# DAC_Schematic.net
KiCad netlist of a schematic drawn in Altium Designer
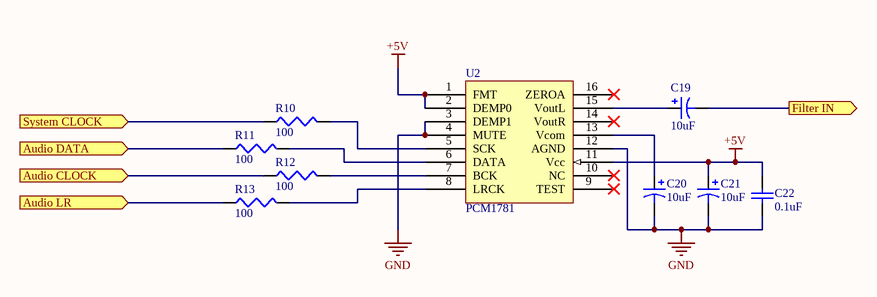
[diagram p0: DAC.Schematic.SchDoc]

(export (version "E")
  (design (tool "Eeschema 10.0.6"))
  (components
    (comp (ref "C19")
      (value "10uF")
      (footprint "CAPC1608N - cap")
      (description "Polarized Capacitor (Radial)")
      (fields (field (name "PUBLISHER") "Altium Limited"))
      (libsource (lib "Miscellaneous Devices") (part "Cap Pol1"))
    )
    (comp (ref "C20")
      (value "10uF")
      (footprint "CAPC1608N - cap")
      (description "Polarized Capacitor (Radial)")
      (fields (field (name "PUBLISHER") "Altium Limited"))
      (libsource (lib "Miscellaneous Devices") (part "Cap Pol1"))
    )
    (comp (ref "C21")
      (value "10uF")
      (footprint "CAPC1608N - cap")
      (description "Polarized Capacitor (Radial)")
      (fields (field (name "PUBLISHER") "Altium Limited"))
      (libsource (lib "Miscellaneous Devices") (part "Cap Pol1"))
    )
    (comp (ref "C22")
      (value "0.1uF")
      (footprint "CAPC1608N - cap")
      (description "Capacitor (Semiconductor SIM Model)")
      (fields (field (name "PUBLISHER") "Altium Limited"))
      (libsource (lib "Miscellaneous Devices") (part "Cap Semi"))
    )
    (comp (ref "R10")
      (value "100")
      (footprint "CAPC1608N")
      (description "Resistor")
      (fields (field (name "PUBLISHER") "Altium Limited"))
      (libsource (lib "Miscellaneous Devices") (part "Res3"))
    )
    (comp (ref "R11")
      (value "100")
      (footprint "CAPC1608N")
      (description "Resistor")
      (fields (field (name "PUBLISHER") "Altium Limited"))
      (libsource (lib "Miscellaneous Devices") (part "Res3"))
    )
    (comp (ref "R12")
      (value "100")
      (footprint "CAPC1608N")
      (description "Resistor")
      (fields (field (name "PUBLISHER") "Altium Limited"))
      (libsource (lib "Miscellaneous Devices") (part "Res3"))
    )
    (comp (ref "R13")
      (value "100")
      (footprint "CAPC1608N")
      (description "Resistor")
      (fields (field (name "PUBLISHER") "Altium Limited"))
      (libsource (lib "Miscellaneous Devices") (part "Res3"))
    )
    (comp (ref "U2")
      (value "PCM1781")
      (footprint "PCM1781")
      (libsource (lib "SynthyTwo.Components") (part "PCM1781 DAC"))
    )
  )
  (nets
    (net (code "1") (name "+5V") (class "Default")
      (node (ref "C21") (pin "1") (pinfunction "1_1") (pintype "passive"))
      (node (ref "C22") (pin "2") (pinfunction "2_2") (pintype "passive"))
      (node (ref "U2") (pin "1") (pinfunction "FMT_1") (pintype "passive"))
      (node (ref "U2") (pin "11") (pinfunction "Vcc_11") (pintype "input"))
      (node (ref "U2") (pin "2") (pinfunction "DEMP0_2") (pintype "passive"))
    )
    (net (code "2") (name "/Audio CLOCK") (class "Default")
      (node (ref "R12") (pin "1") (pinfunction "1_1") (pintype "passive"))
    )
    (net (code "3") (name "/Audio DATA") (class "Default")
      (node (ref "R11") (pin "1") (pinfunction "1_1") (pintype "passive"))
    )
    (net (code "4") (name "/Audio LR") (class "Default")
      (node (ref "R13") (pin "1") (pinfunction "1_1") (pintype "passive"))
    )
    (net (code "5") (name "/Filter IN") (class "Default")
      (node (ref "C19") (pin "2") (pinfunction "2_2") (pintype "passive"))
    )
    (net (code "6") (name "/System CLOCK") (class "Default")
      (node (ref "R10") (pin "1") (pinfunction "1_1") (pintype "passive"))
    )
    (net (code "7") (name "GND") (class "Default")
      (node (ref "C20") (pin "2") (pinfunction "2_2") (pintype "passive"))
      (node (ref "C21") (pin "2") (pinfunction "2_2") (pintype "passive"))
      (node (ref "C22") (pin "1") (pinfunction "1_1") (pintype "passive"))
      (node (ref "U2") (pin "12") (pinfunction "AGND_12") (pintype "passive"))
      (node (ref "U2") (pin "3") (pinfunction "DEMP1_3") (pintype "passive"))
      (node (ref "U2") (pin "4") (pinfunction "MUTE_4") (pintype "passive"))
    )
    (net (code "8") (name "Net-(U2-BCK)") (class "Default")
      (node (ref "R12") (pin "2") (pinfunction "2_2") (pintype "passive"))
      (node (ref "U2") (pin "7") (pinfunction "BCK_7") (pintype "passive"))
    )
    (net (code "9") (name "Net-(U2-DATA)") (class "Default")
      (node (ref "R11") (pin "2") (pinfunction "2_2") (pintype "passive"))
      (node (ref "U2") (pin "6") (pinfunction "DATA_6") (pintype "passive"))
    )
    (net (code "10") (name "Net-(U2-LRCK)") (class "Default")
      (node (ref "R13") (pin "2") (pinfunction "2_2") (pintype "passive"))
      (node (ref "U2") (pin "8") (pinfunction "LRCK_8") (pintype "passive"))
    )
    (net (code "11") (name "Net-(U2-SCK)") (class "Default")
      (node (ref "R10") (pin "2") (pinfunction "2_2") (pintype "passive"))
      (node (ref "U2") (pin "5") (pinfunction "SCK_5") (pintype "passive"))
    )
    (net (code "12") (name "Net-(U2-Vcom)") (class "Default")
      (node (ref "C20") (pin "1") (pinfunction "1_1") (pintype "passive"))
      (node (ref "U2") (pin "13") (pinfunction "Vcom_13") (pintype "passive"))
    )
    (net (code "13") (name "Net-(U2-VoutL)") (class "Default")
      (node (ref "C19") (pin "1") (pinfunction "1_1") (pintype "passive"))
      (node (ref "U2") (pin "15") (pinfunction "VoutL_15") (pintype "passive"))
    )
    (net (code "14") (name "unconnected-(U2-NC-Pad10)") (class "Default")
      (node (ref "U2") (pin "10") (pinfunction "NC_10") (pintype "passive+no_connect"))
    )
    (net (code "15") (name "unconnected-(U2-TEST-Pad9)") (class "Default")
      (node (ref "U2") (pin "9") (pinfunction "TEST_9") (pintype "passive+no_connect"))
    )
    (net (code "16") (name "unconnected-(U2-VoutR-Pad14)") (class "Default")
      (node (ref "U2") (pin "14") (pinfunction "VoutR_14") (pintype "passive+no_connect"))
    )
    (net (code "17") (name "unconnected-(U2-ZEROA-Pad16)") (class "Default")
      (node (ref "U2") (pin "16") (pinfunction "ZEROA_16") (pintype "passive+no_connect"))
    )
  )
)
